# 91_Debug_UART_JTAG.net
KiCad netlist of a schematic drawn in Altium Designer
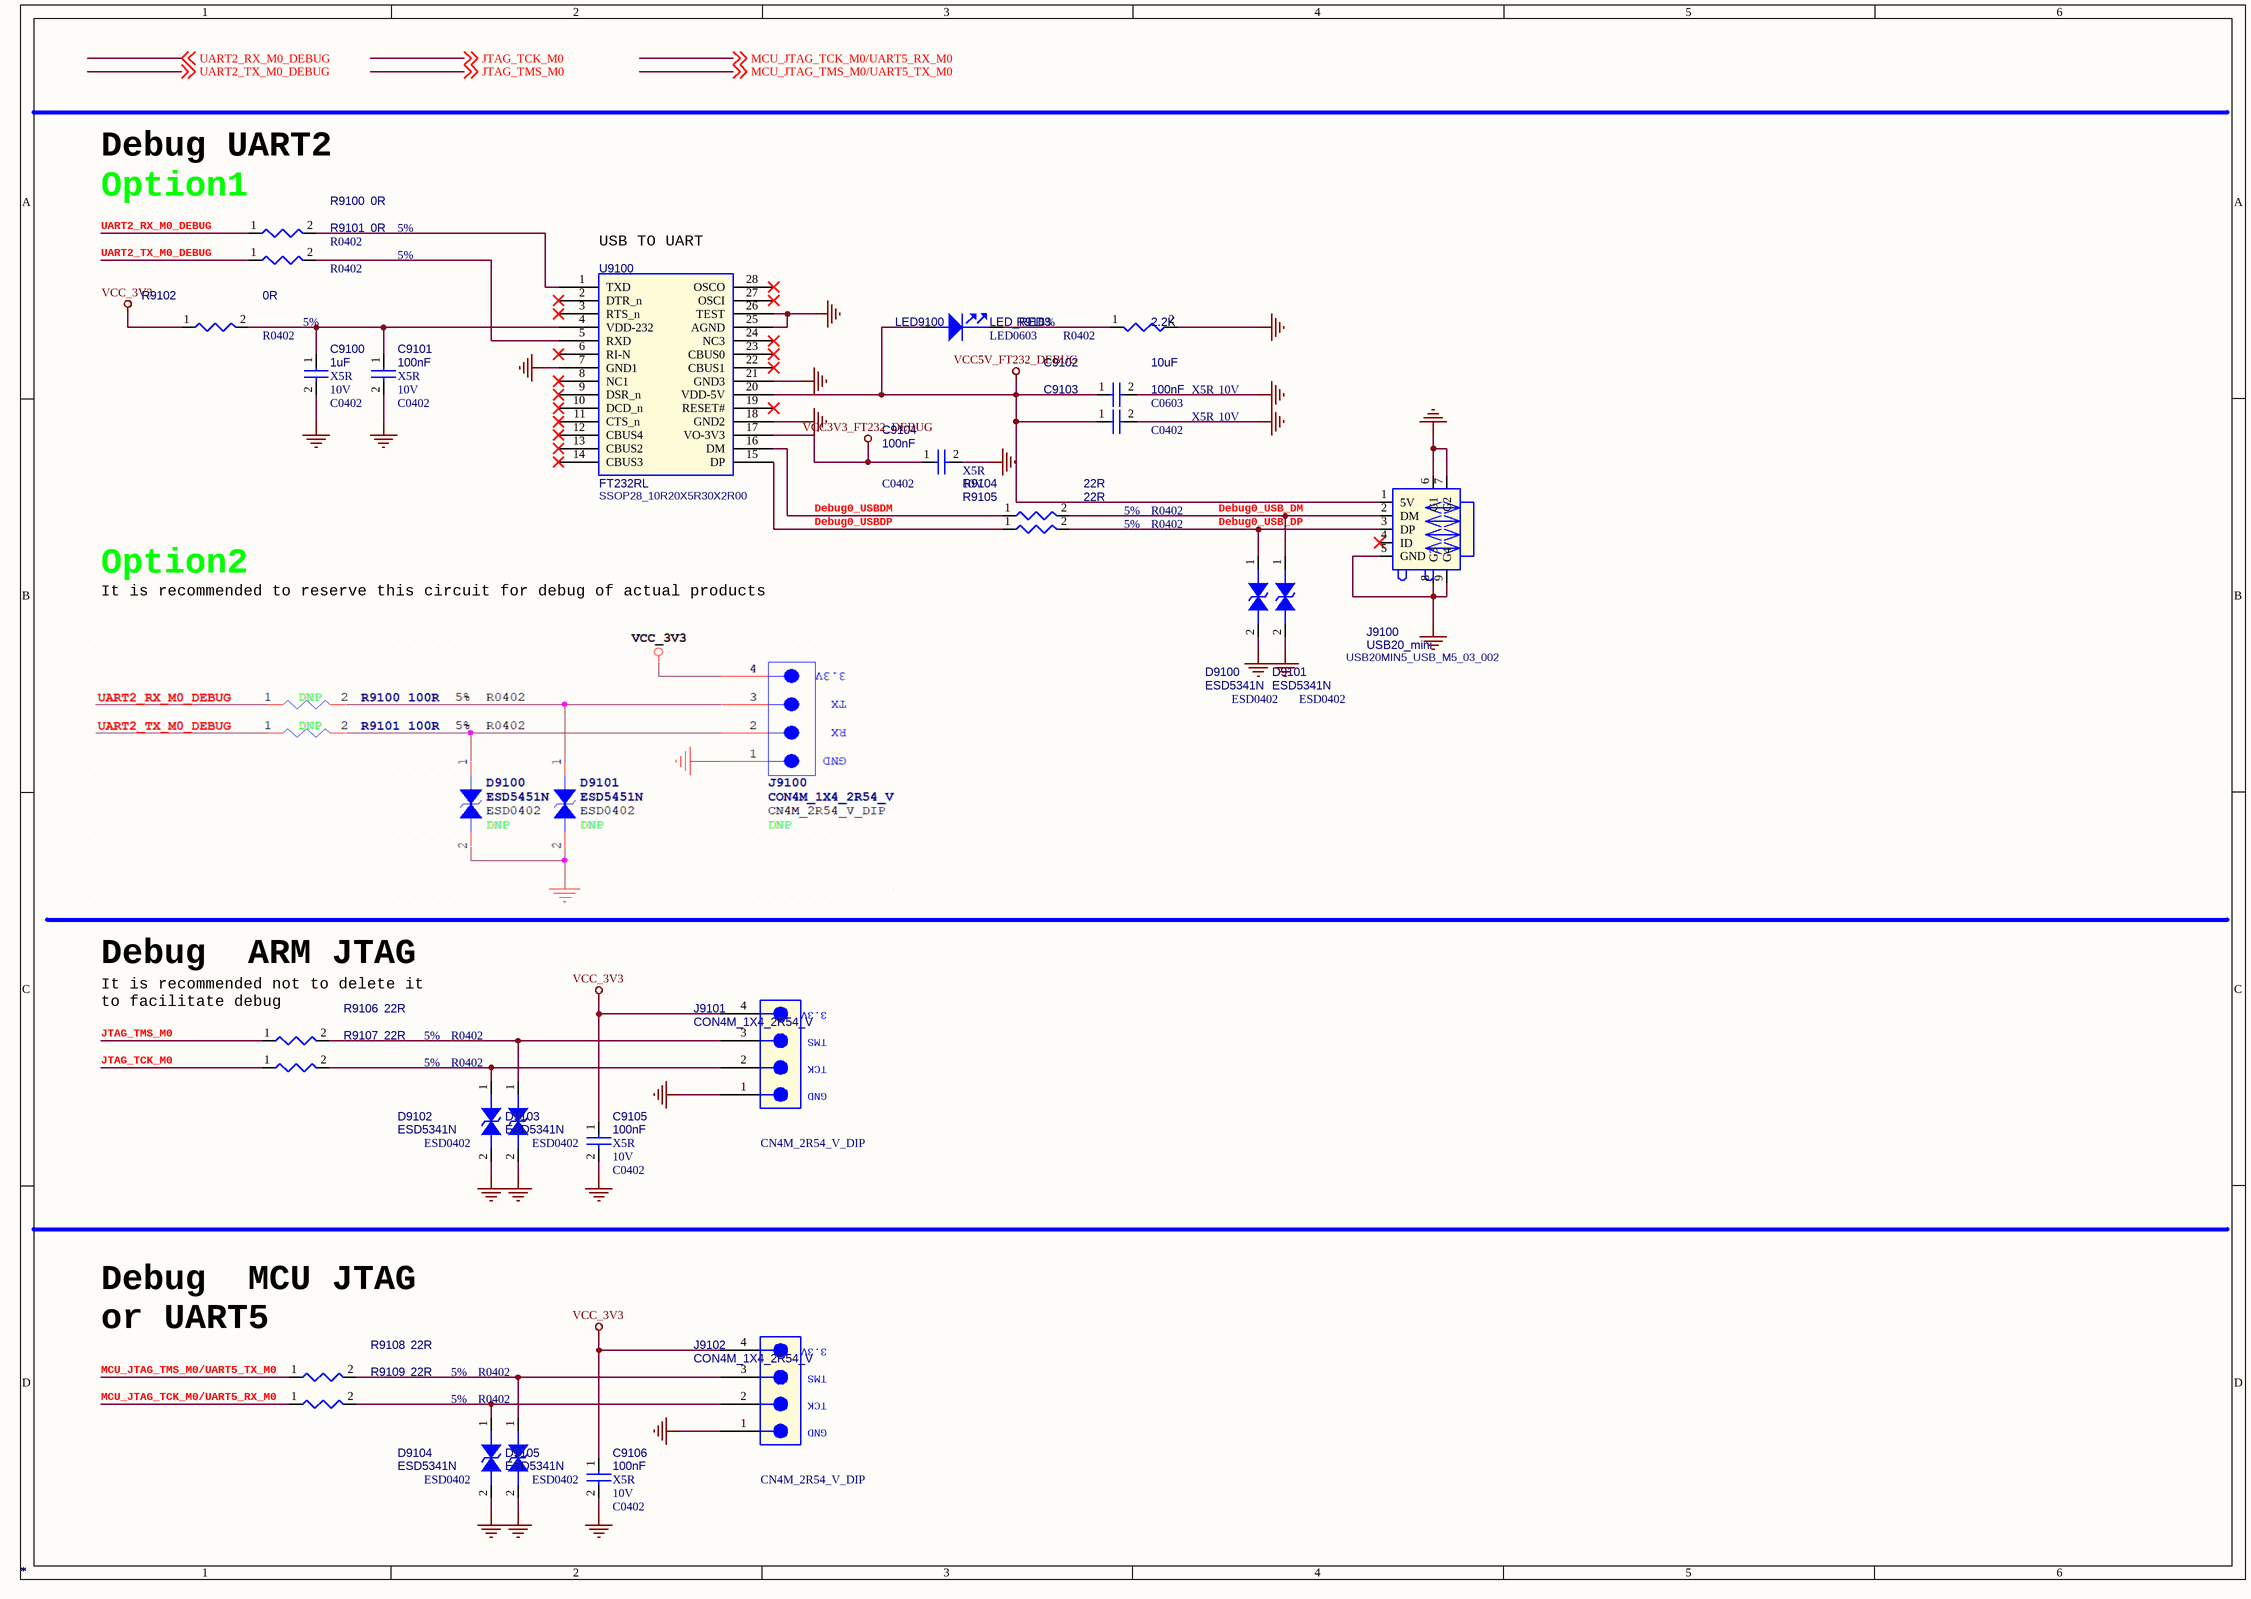
[diagram p0: 91.Debug UART_JTAG.SchDoc]

(export (version "E")
  (design (tool "Eeschema 10.0.6"))
  (components
    (comp (ref "C9100")
      (value "*")
      (footprint "C0402")
      (description "cap,1.00uF,+/-10%,10V,X5R,C0402")
      (fields
        (field (name "VOLTAGE") "10V")
        (field (name "PCB FOOTPRINT") "C0402")
        (field (name "DIELECTRIC") "X5R")
        (field (name "MANUFACTURER") "TDK")
        (field (name "TOLERANCE") "10%")
        (field (name "ALTIUM_UNNAMED_1") "1uF")
        (field (name "CREATED BY") "JJJ")
      )
      (libsource (lib "*") (part "CAP NP"))
    )
    (comp (ref "C9101")
      (value "*")
      (footprint "C0402")
      (description "cap,100.00nF,+/-10%,10V,X5R,C0402")
      (fields
        (field (name "VOLTAGE") "10V")
        (field (name "PCB FOOTPRINT") "C0402")
        (field (name "DIELECTRIC") "X5R")
        (field (name "TOLERANCE") "10%")
        (field (name "MANUFACTURER") "TDK")
        (field (name "ALTIUM_UNNAMED_1") "100nF")
        (field (name "CREATED BY") "JJJ")
      )
      (libsource (lib "*") (part "CAP NP"))
    )
    (comp (ref "C9102")
      (value "*")
      (footprint "C0603")
      (description "cap,10.00uF,+/-10%,10V,X5R,C0603")
      (fields
        (field (name "VOLTAGE") "10V")
        (field (name "PCB FOOTPRINT") "C0603")
        (field (name "DIELECTRIC") "X5R")
        (field (name "TOLERANCE") "10%")
        (field (name "MANUFACTURER") "TDK")
        (field (name "ALTIUM_UNNAMED_1") "10uF")
        (field (name "CREATED BY") "JJJ")
      )
      (libsource (lib "*") (part "CAP NP"))
    )
    (comp (ref "C9103")
      (value "*")
      (footprint "C0402")
      (description "cap,100.00nF,+/-10%,10V,X5R,C0402")
      (fields
        (field (name "VOLTAGE") "10V")
        (field (name "PCB FOOTPRINT") "C0402")
        (field (name "DIELECTRIC") "X5R")
        (field (name "TOLERANCE") "10%")
        (field (name "MANUFACTURER") "TDK")
        (field (name "ALTIUM_UNNAMED_1") "100nF")
        (field (name "CREATED BY") "JJJ")
      )
      (libsource (lib "*") (part "CAP NP"))
    )
    (comp (ref "C9104")
      (value "*")
      (footprint "C0402")
      (description "cap,100.00nF,+/-10%,10V,X5R,C0402")
      (fields
        (field (name "VOLTAGE") "10V")
        (field (name "PCB FOOTPRINT") "C0402")
        (field (name "DIELECTRIC") "X5R")
        (field (name "MANUFACTURER") "TDK")
        (field (name "TOLERANCE") "10%")
        (field (name "ALTIUM_UNNAMED_1") "100nF")
        (field (name "CREATED BY") "JJJ")
      )
      (libsource (lib "*") (part "CAP NP"))
    )
    (comp (ref "C9105")
      (value "*")
      (footprint "C0402")
      (description "cap,100.00nF,+/-10%,10V,X5R,C0402")
      (fields
        (field (name "VOLTAGE") "10V")
        (field (name "PCB FOOTPRINT") "C0402")
        (field (name "DIELECTRIC") "X5R")
        (field (name "MANUFACTURER") "TDK")
        (field (name "TOLERANCE") "10%")
        (field (name "ALTIUM_UNNAMED_1") "100nF")
        (field (name "CREATED BY") "JJJ")
      )
      (libsource (lib "*") (part "CAP NP"))
    )
    (comp (ref "C9106")
      (value "*")
      (footprint "C0402")
      (description "cap,100.00nF,+/-10%,10V,X5R,C0402")
      (fields
        (field (name "VOLTAGE") "10V")
        (field (name "PCB FOOTPRINT") "C0402")
        (field (name "DIELECTRIC") "X5R")
        (field (name "MANUFACTURER") "TDK")
        (field (name "TOLERANCE") "10%")
        (field (name "ALTIUM_UNNAMED_1") "100nF")
        (field (name "CREATED BY") "JJJ")
      )
      (libsource (lib "*") (part "CAP NP"))
    )
    (comp (ref "D9100")
      (value "*")
      (footprint "ESD0402")
      (description "1-Line, Bi-directional, Transient Voltage Suppressors.1pF.")
      (fields
        (field (name "PCB FOOTPRINT") "ESD0402")
        (field (name "MANUFACTURER") "WillSemi(О¤¶ы°лµјМе)")
        (field (name "ALTIUM_UNNAMED_1") "ESD5341N")
        (field (name "CREATED BY") "JJJ")
      )
      (libsource (lib "*") (part "DIODE BI_DIR TRIG"))
    )
    (comp (ref "D9101")
      (value "*")
      (footprint "ESD0402")
      (description "1-Line, Bi-directional, Transient Voltage Suppressors.1pF.")
      (fields
        (field (name "PCB FOOTPRINT") "ESD0402")
        (field (name "MANUFACTURER") "WillSemi(О¤¶ы°лµјМе)")
        (field (name "ALTIUM_UNNAMED_1") "ESD5341N")
        (field (name "CREATED BY") "JJJ")
      )
      (libsource (lib "*") (part "DIODE BI_DIR TRIG"))
    )
    (comp (ref "D9102")
      (value "*")
      (footprint "ESD0402")
      (description "1-Line, Bi-directional, Transient Voltage Suppressors.1pF.")
      (fields
        (field (name "PCB FOOTPRINT") "ESD0402")
        (field (name "MANUFACTURER") "WillSemi(О¤¶ы°лµјМе)")
        (field (name "ALTIUM_UNNAMED_1") "ESD5341N")
        (field (name "CREATED BY") "JJJ")
      )
      (libsource (lib "*") (part "DIODE BI_DIR TRIG"))
    )
    (comp (ref "D9103")
      (value "*")
      (footprint "ESD0402")
      (description "1-Line, Bi-directional, Transient Voltage Suppressors.1pF.")
      (fields
        (field (name "PCB FOOTPRINT") "ESD0402")
        (field (name "MANUFACTURER") "WillSemi(О¤¶ы°лµјМе)")
        (field (name "ALTIUM_UNNAMED_1") "ESD5341N")
        (field (name "CREATED BY") "JJJ")
      )
      (libsource (lib "*") (part "DIODE BI_DIR TRIG"))
    )
    (comp (ref "D9104")
      (value "*")
      (footprint "ESD0402")
      (description "1-Line, Bi-directional, Transient Voltage Suppressors.1pF.")
      (fields
        (field (name "PCB FOOTPRINT") "ESD0402")
        (field (name "MANUFACTURER") "WillSemi(О¤¶ы°лµјМе)")
        (field (name "ALTIUM_UNNAMED_1") "ESD5341N")
        (field (name "CREATED BY") "JJJ")
      )
      (libsource (lib "*") (part "DIODE BI_DIR TRIG"))
    )
    (comp (ref "D9105")
      (value "*")
      (footprint "ESD0402")
      (description "1-Line, Bi-directional, Transient Voltage Suppressors.1pF.")
      (fields
        (field (name "PCB FOOTPRINT") "ESD0402")
        (field (name "MANUFACTURER") "WillSemi(О¤¶ы°лµјМе)")
        (field (name "ALTIUM_UNNAMED_1") "ESD5341N")
        (field (name "CREATED BY") "JJJ")
      )
      (libsource (lib "*") (part "DIODE BI_DIR TRIG"))
    )
    (comp (ref "J9100")
      (value "*")
      (footprint "USB20MIN5_USB_M5_03_002")
      (description "USB2.0 MiniРНОФКЅІаІеДёЧщЈ¬Мщєё")
      (fields
        (field (name "PCB FOOTPRINT") "USB20MIN5_USB_M5_03_002")
        (field (name "MANUFACTURER PART NUMBER") "USB-M5-03-002")
        (field (name "MANUFACTURER") "НъїЖґп")
        (field (name "ALTIUM_UNNAMED_1") "USB20_mini")
        (field (name "CREATED BY") "JJJ")
      )
      (libsource (lib "*") (part "USB20_MINI"))
    )
    (comp (ref "J9101")
      (value "*")
      (footprint "CN4M_2R54_V_DIP")
      (fields
        (field (name "PCB FOOTPRINT") "CN4M_2R54_V_DIP")
        (field (name "ALTIUM_UNNAMED_1") "CON4M_1X4_2R54_V")
      )
      (libsource (lib "*") (part "HEADER 4_0"))
    )
    (comp (ref "J9102")
      (value "*")
      (footprint "CN4M_2R54_V_DIP")
      (fields
        (field (name "PCB FOOTPRINT") "CN4M_2R54_V_DIP")
        (field (name "ALTIUM_UNNAMED_1") "CON4M_1X4_2R54_V")
      )
      (libsource (lib "*") (part "HEADER 4_0"))
    )
    (comp (ref "LED9100")
      (value "*")
      (footprint "LED0603")
      (description "МщЖ¬LEDµЖЈ¬0603Ј¬ємЙ«")
      (fields
        (field (name "PCB FOOTPRINT") "LED0603")
        (field (name "ALTIUM_UNNAMED_1") "LED_RED")
        (field (name "CREATED BY") "JJJ")
      )
      (libsource (lib "*") (part "LED"))
    )
    (comp (ref "R9100")
      (value "*")
      (footprint "R0402")
      (description "НЁУГєсД¤µзЧи,0R,+/-5%,R0402,1/16W.")
      (fields
        (field (name "PCB FOOTPRINT") "R0402")
        (field (name "TOLERANCE") "5%")
        (field (name "MANUFACTURER") "YAGEO")
        (field (name "ALTIUM_UNNAMED_1") "0R")
        (field (name "CREATED BY") "YTL")
      )
      (libsource (lib "*") (part "RESISTOR_Dup1"))
    )
    (comp (ref "R9101")
      (value "*")
      (footprint "R0402")
      (description "НЁУГєсД¤µзЧи,0R,+/-5%,R0402,1/16W.")
      (fields
        (field (name "PCB FOOTPRINT") "R0402")
        (field (name "TOLERANCE") "5%")
        (field (name "MANUFACTURER") "YAGEO")
        (field (name "ALTIUM_UNNAMED_1") "0R")
        (field (name "CREATED BY") "YTL")
      )
      (libsource (lib "*") (part "RESISTOR_Dup1"))
    )
    (comp (ref "R9102")
      (value "*")
      (footprint "R0402")
      (description "НЁУГєсД¤µзЧи,0R,+/-5%,R0402,1/16W.")
      (fields
        (field (name "PCB FOOTPRINT") "R0402")
        (field (name "TOLERANCE") "5%")
        (field (name "MANUFACTURER") "YAGEO")
        (field (name "ALTIUM_UNNAMED_1") "0R")
        (field (name "CREATED BY") "YTL")
      )
      (libsource (lib "*") (part "RESISTOR_Dup1"))
    )
    (comp (ref "R9103")
      (value "*")
      (footprint "R0402")
      (description "НЁУГєсД¤µзЧи,2K2,+/-5%,R0402,1/16W.")
      (fields
        (field (name "PCB FOOTPRINT") "R0402")
        (field (name "TOLERANCE") "5%")
        (field (name "MANUFACTURER") "YAGEO")
        (field (name "ALTIUM_UNNAMED_1") "2.2K")
        (field (name "CREATED BY") "YTL")
      )
      (libsource (lib "*") (part "RESISTOR_Dup1"))
    )
    (comp (ref "R9104")
      (value "*")
      (footprint "R0402")
      (description "НЁУГєсД¤µзЧи,22R,+/-5%,R0402,1/16W.")
      (fields
        (field (name "PCB FOOTPRINT") "R0402")
        (field (name "TOLERANCE") "5%")
        (field (name "MANUFACTURER") "YAGEO")
        (field (name "ALTIUM_UNNAMED_1") "22R")
        (field (name "CREATED BY") "YTL")
      )
      (libsource (lib "*") (part "RESISTOR_Dup1"))
    )
    (comp (ref "R9105")
      (value "*")
      (footprint "R0402")
      (description "НЁУГєсД¤µзЧи,22R,+/-5%,R0402,1/16W.")
      (fields
        (field (name "PCB FOOTPRINT") "R0402")
        (field (name "TOLERANCE") "5%")
        (field (name "MANUFACTURER") "YAGEO")
        (field (name "ALTIUM_UNNAMED_1") "22R")
        (field (name "CREATED BY") "YTL")
      )
      (libsource (lib "*") (part "RESISTOR_Dup1"))
    )
    (comp (ref "R9106")
      (value "*")
      (footprint "R0402")
      (description "НЁУГєсД¤µзЧи,22R,+/-5%,R0402,1/16W.")
      (fields
        (field (name "PCB FOOTPRINT") "R0402")
        (field (name "TOLERANCE") "5%")
        (field (name "MANUFACTURER") "YAGEO")
        (field (name "ALTIUM_UNNAMED_1") "22R")
        (field (name "CREATED BY") "YTL")
      )
      (libsource (lib "*") (part "RESISTOR_Dup1"))
    )
    (comp (ref "R9107")
      (value "*")
      (footprint "R0402")
      (description "НЁУГєсД¤µзЧи,22R,+/-5%,R0402,1/16W.")
      (fields
        (field (name "PCB FOOTPRINT") "R0402")
        (field (name "TOLERANCE") "5%")
        (field (name "MANUFACTURER") "YAGEO")
        (field (name "ALTIUM_UNNAMED_1") "22R")
        (field (name "CREATED BY") "YTL")
      )
      (libsource (lib "*") (part "RESISTOR_Dup1"))
    )
    (comp (ref "R9108")
      (value "*")
      (footprint "R0402")
      (description "НЁУГєсД¤µзЧи,22R,+/-5%,R0402,1/16W.")
      (fields
        (field (name "PCB FOOTPRINT") "R0402")
        (field (name "TOLERANCE") "5%")
        (field (name "MANUFACTURER") "YAGEO")
        (field (name "ALTIUM_UNNAMED_1") "22R")
        (field (name "CREATED BY") "YTL")
      )
      (libsource (lib "*") (part "RESISTOR_Dup1"))
    )
    (comp (ref "R9109")
      (value "*")
      (footprint "R0402")
      (description "НЁУГєсД¤µзЧи,22R,+/-5%,R0402,1/16W.")
      (fields
        (field (name "PCB FOOTPRINT") "R0402")
        (field (name "TOLERANCE") "5%")
        (field (name "MANUFACTURER") "YAGEO")
        (field (name "ALTIUM_UNNAMED_1") "22R")
        (field (name "CREATED BY") "YTL")
      )
      (libsource (lib "*") (part "RESISTOR_Dup1"))
    )
    (comp (ref "U9100")
      (value "*")
      (footprint "SSOP28")
      (description "Single chip USB to asynchronous serial data transfer interface.")
      (fields
        (field (name "PCB FOOTPRINT") "SSOP28_10R20X5R30X2R00")
        (field (name "MANUFACTURER") "FTDI Chip")
        (field (name "ALTIUM_UNNAMED_1") "FT232RL")
        (field (name "CREATED BY") "JJJ")
      )
      (libsource (lib "*") (part "Interface_FT232RL"))
    )
  )
  (nets
    (net (code "1") (name "/Debug0_USBDM") (class "Default")
      (node (ref "R9104") (pin "1") (pinfunction "1_1") (pintype "passive"))
      (node (ref "U9100") (pin "16") (pinfunction "DM_16") (pintype "passive"))
    )
    (net (code "2") (name "/Debug0_USBDP") (class "Default")
      (node (ref "R9105") (pin "1") (pinfunction "1_1") (pintype "passive"))
      (node (ref "U9100") (pin "15") (pinfunction "DP_15") (pintype "passive"))
    )
    (net (code "3") (name "/Debug0_USB_DM") (class "Default")
      (node (ref "D9101") (pin "1") (pinfunction "1_1") (pintype "passive"))
      (node (ref "J9100") (pin "2") (pinfunction "DM_2") (pintype "passive"))
      (node (ref "R9104") (pin "2") (pinfunction "2_2") (pintype "passive"))
    )
    (net (code "4") (name "/Debug0_USB_DP") (class "Default")
      (node (ref "D9100") (pin "1") (pinfunction "1_1") (pintype "passive"))
      (node (ref "J9100") (pin "3") (pinfunction "DP_3") (pintype "passive"))
      (node (ref "R9105") (pin "2") (pinfunction "2_2") (pintype "passive"))
    )
    (net (code "5") (name "GND") (class "Default")
      (node (ref "C9100") (pin "2") (pinfunction "2_2") (pintype "passive"))
      (node (ref "C9101") (pin "2") (pinfunction "2_2") (pintype "passive"))
      (node (ref "C9102") (pin "2") (pinfunction "2_2") (pintype "passive"))
      (node (ref "C9103") (pin "2") (pinfunction "2_2") (pintype "passive"))
      (node (ref "C9104") (pin "2") (pinfunction "2_2") (pintype "passive"))
      (node (ref "C9105") (pin "2") (pinfunction "2_2") (pintype "passive"))
      (node (ref "C9106") (pin "2") (pinfunction "2_2") (pintype "passive"))
      (node (ref "D9100") (pin "2") (pinfunction "2_2") (pintype "passive"))
      (node (ref "D9101") (pin "2") (pinfunction "2_2") (pintype "passive"))
      (node (ref "D9102") (pin "2") (pinfunction "2_2") (pintype "passive"))
      (node (ref "D9103") (pin "2") (pinfunction "2_2") (pintype "passive"))
      (node (ref "D9104") (pin "2") (pinfunction "2_2") (pintype "passive"))
      (node (ref "D9105") (pin "2") (pinfunction "2_2") (pintype "passive"))
      (node (ref "J9100") (pin "5") (pinfunction "GND_5") (pintype "passive"))
      (node (ref "J9100") (pin "6") (pinfunction "G1_6") (pintype "passive"))
      (node (ref "J9100") (pin "7") (pinfunction "G2_7") (pintype "passive"))
      (node (ref "J9100") (pin "8") (pinfunction "G3_8") (pintype "passive"))
      (node (ref "J9100") (pin "9") (pinfunction "G4_9") (pintype "passive"))
      (node (ref "J9101") (pin "1") (pinfunction "1_1") (pintype "passive"))
      (node (ref "J9102") (pin "1") (pinfunction "1_1") (pintype "passive"))
      (node (ref "R9103") (pin "2") (pinfunction "2_2") (pintype "passive"))
      (node (ref "U9100") (pin "18") (pinfunction "GND2_18") (pintype "passive"))
      (node (ref "U9100") (pin "21") (pinfunction "GND3_21") (pintype "passive"))
      (node (ref "U9100") (pin "25") (pinfunction "AGND_25") (pintype "passive"))
      (node (ref "U9100") (pin "26") (pinfunction "TEST_26") (pintype "passive"))
      (node (ref "U9100") (pin "7") (pinfunction "GND1_7") (pintype "passive"))
    )
    (net (code "6") (name "JTAG_TCK_M0") (class "Default")
      (node (ref "R9107") (pin "1") (pinfunction "1_1") (pintype "passive"))
    )
    (net (code "7") (name "JTAG_TMS_M0") (class "Default")
      (node (ref "R9106") (pin "1") (pinfunction "1_1") (pintype "passive"))
    )
    (net (code "8") (name "MCU_JTAG_TCK_M0{slash}UART5_RX_M0") (class "Default")
      (node (ref "R9109") (pin "1") (pinfunction "1_1") (pintype "passive"))
    )
    (net (code "9") (name "MCU_JTAG_TMS_M0{slash}UART5_TX_M0") (class "Default")
      (node (ref "R9108") (pin "1") (pinfunction "1_1") (pintype "passive"))
    )
    (net (code "10") (name "Net-(D9103-Pad1)") (class "Default")
      (node (ref "D9103") (pin "1") (pinfunction "1_1") (pintype "passive"))
      (node (ref "J9101") (pin "3") (pinfunction "3_3") (pintype "passive"))
      (node (ref "R9106") (pin "2") (pinfunction "2_2") (pintype "passive"))
    )
    (net (code "11") (name "Net-(D9105-Pad1)") (class "Default")
      (node (ref "D9105") (pin "1") (pinfunction "1_1") (pintype "passive"))
      (node (ref "J9102") (pin "3") (pinfunction "3_3") (pintype "passive"))
      (node (ref "R9108") (pin "2") (pinfunction "2_2") (pintype "passive"))
    )
    (net (code "12") (name "Net-(J9101-RX)") (class "Default")
      (node (ref "D9102") (pin "1") (pinfunction "1_1") (pintype "passive"))
      (node (ref "J9101") (pin "2") (pinfunction "RX_2") (pintype "passive"))
      (node (ref "R9107") (pin "2") (pinfunction "2_2") (pintype "passive"))
    )
    (net (code "13") (name "Net-(J9102-RX)") (class "Default")
      (node (ref "D9104") (pin "1") (pinfunction "1_1") (pintype "passive"))
      (node (ref "J9102") (pin "2") (pinfunction "RX_2") (pintype "passive"))
      (node (ref "R9109") (pin "2") (pinfunction "2_2") (pintype "passive"))
    )
    (net (code "14") (name "Net-(LED9100-CATHODE)") (class "Default")
      (node (ref "LED9100") (pin "2") (pinfunction "CATHODE_2") (pintype "passive"))
      (node (ref "R9103") (pin "1") (pinfunction "1_1") (pintype "passive"))
    )
    (net (code "15") (name "Net-(U9100-RXD)") (class "Default")
      (node (ref "R9101") (pin "2") (pinfunction "2_2") (pintype "passive"))
      (node (ref "U9100") (pin "5") (pinfunction "RXD_5") (pintype "passive"))
    )
    (net (code "16") (name "Net-(U9100-TXD)") (class "Default")
      (node (ref "R9100") (pin "2") (pinfunction "2_2") (pintype "passive"))
      (node (ref "U9100") (pin "1") (pinfunction "TXD_1") (pintype "passive"))
    )
    (net (code "17") (name "Net-(U9100-VDD-232)") (class "Default")
      (node (ref "C9100") (pin "1") (pinfunction "1_1") (pintype "passive"))
      (node (ref "C9101") (pin "1") (pinfunction "1_1") (pintype "passive"))
      (node (ref "R9102") (pin "2") (pinfunction "2_2") (pintype "passive"))
      (node (ref "U9100") (pin "4") (pinfunction "VDD-232_4") (pintype "passive"))
    )
    (net (code "18") (name "UART2_RX_M0_DEBUG") (class "Default")
      (node (ref "R9100") (pin "1") (pinfunction "1_1") (pintype "passive"))
    )
    (net (code "19") (name "UART2_TX_M0_DEBUG") (class "Default")
      (node (ref "R9101") (pin "1") (pinfunction "1_1") (pintype "passive"))
    )
    (net (code "20") (name "VCC3V3_FT232_DEBUG") (class "Default")
      (node (ref "C9104") (pin "1") (pinfunction "1_1") (pintype "passive"))
      (node (ref "U9100") (pin "17") (pinfunction "VO-3V3_17") (pintype "passive"))
    )
    (net (code "21") (name "VCC5V_FT232_DEBUG") (class "Default")
      (node (ref "C9102") (pin "1") (pinfunction "1_1") (pintype "passive"))
      (node (ref "C9103") (pin "1") (pinfunction "1_1") (pintype "passive"))
      (node (ref "J9100") (pin "1") (pinfunction "5V_1") (pintype "passive"))
      (node (ref "LED9100") (pin "1") (pinfunction "ANODE_1") (pintype "passive"))
      (node (ref "U9100") (pin "20") (pinfunction "VDD-5V_20") (pintype "passive"))
    )
    (net (code "22") (name "VCC_3V3") (class "Default")
      (node (ref "C9105") (pin "1") (pinfunction "1_1") (pintype "passive"))
      (node (ref "C9106") (pin "1") (pinfunction "1_1") (pintype "passive"))
      (node (ref "J9101") (pin "4") (pinfunction "4_4") (pintype "passive"))
      (node (ref "J9102") (pin "4") (pinfunction "4_4") (pintype "passive"))
      (node (ref "R9102") (pin "1") (pinfunction "1_1") (pintype "passive"))
    )
    (net (code "23") (name "unconnected-(J9100-ID-Pad4)") (class "Default")
      (node (ref "J9100") (pin "4") (pinfunction "ID_4") (pintype "passive+no_connect"))
    )
    (net (code "24") (name "unconnected-(U9100-CBUS0-Pad23)") (class "Default")
      (node (ref "U9100") (pin "23") (pinfunction "CBUS0_23") (pintype "passive+no_connect"))
    )
    (net (code "25") (name "unconnected-(U9100-CBUS1-Pad22)") (class "Default")
      (node (ref "U9100") (pin "22") (pinfunction "CBUS1_22") (pintype "passive+no_connect"))
    )
    (net (code "26") (name "unconnected-(U9100-CBUS2-Pad13)") (class "Default")
      (node (ref "U9100") (pin "13") (pinfunction "CBUS2_13") (pintype "passive+no_connect"))
    )
    (net (code "27") (name "unconnected-(U9100-CBUS3-Pad14)") (class "Default")
      (node (ref "U9100") (pin "14") (pinfunction "CBUS3_14") (pintype "passive+no_connect"))
    )
    (net (code "28") (name "unconnected-(U9100-CBUS4-Pad12)") (class "Default")
      (node (ref "U9100") (pin "12") (pinfunction "CBUS4_12") (pintype "passive+no_connect"))
    )
    (net (code "29") (name "unconnected-(U9100-CTS_n-Pad11)") (class "Default")
      (node (ref "U9100") (pin "11") (pinfunction "CTS_n_11") (pintype "passive+no_connect"))
    )
    (net (code "30") (name "unconnected-(U9100-DCD_n-Pad10)") (class "Default")
      (node (ref "U9100") (pin "10") (pinfunction "DCD_n_10") (pintype "passive+no_connect"))
    )
    (net (code "31") (name "unconnected-(U9100-DSR_n-Pad9)") (class "Default")
      (node (ref "U9100") (pin "9") (pinfunction "DSR_n_9") (pintype "passive+no_connect"))
    )
    (net (code "32") (name "unconnected-(U9100-DTR_n-Pad2)") (class "Default")
      (node (ref "U9100") (pin "2") (pinfunction "DTR_n_2") (pintype "passive+no_connect"))
    )
    (net (code "33") (name "unconnected-(U9100-NC1-Pad8)") (class "Default")
      (node (ref "U9100") (pin "8") (pinfunction "NC1_8") (pintype "passive+no_connect"))
    )
    (net (code "34") (name "unconnected-(U9100-NC3-Pad24)") (class "Default")
      (node (ref "U9100") (pin "24") (pinfunction "NC3_24") (pintype "passive+no_connect"))
    )
    (net (code "35") (name "unconnected-(U9100-OSCI-Pad27)") (class "Default")
      (node (ref "U9100") (pin "27") (pinfunction "OSCI_27") (pintype "passive+no_connect"))
    )
    (net (code "36") (name "unconnected-(U9100-OSCO-Pad28)") (class "Default")
      (node (ref "U9100") (pin "28") (pinfunction "OSCO_28") (pintype "passive+no_connect"))
    )
    (net (code "37") (name "unconnected-(U9100-RESET#-Pad19)") (class "Default")
      (node (ref "U9100") (pin "19") (pinfunction "RESET#_19") (pintype "passive+no_connect"))
    )
    (net (code "38") (name "unconnected-(U9100-RI-N-Pad6)") (class "Default")
      (node (ref "U9100") (pin "6") (pinfunction "RI-N_6") (pintype "passive+no_connect"))
    )
    (net (code "39") (name "unconnected-(U9100-RTS_n-Pad3)") (class "Default")
      (node (ref "U9100") (pin "3") (pinfunction "RTS_n_3") (pintype "passive+no_connect"))
    )
  )
)
